# AMP_LO.net
KiCad netlist of a schematic drawn in Altium Designer
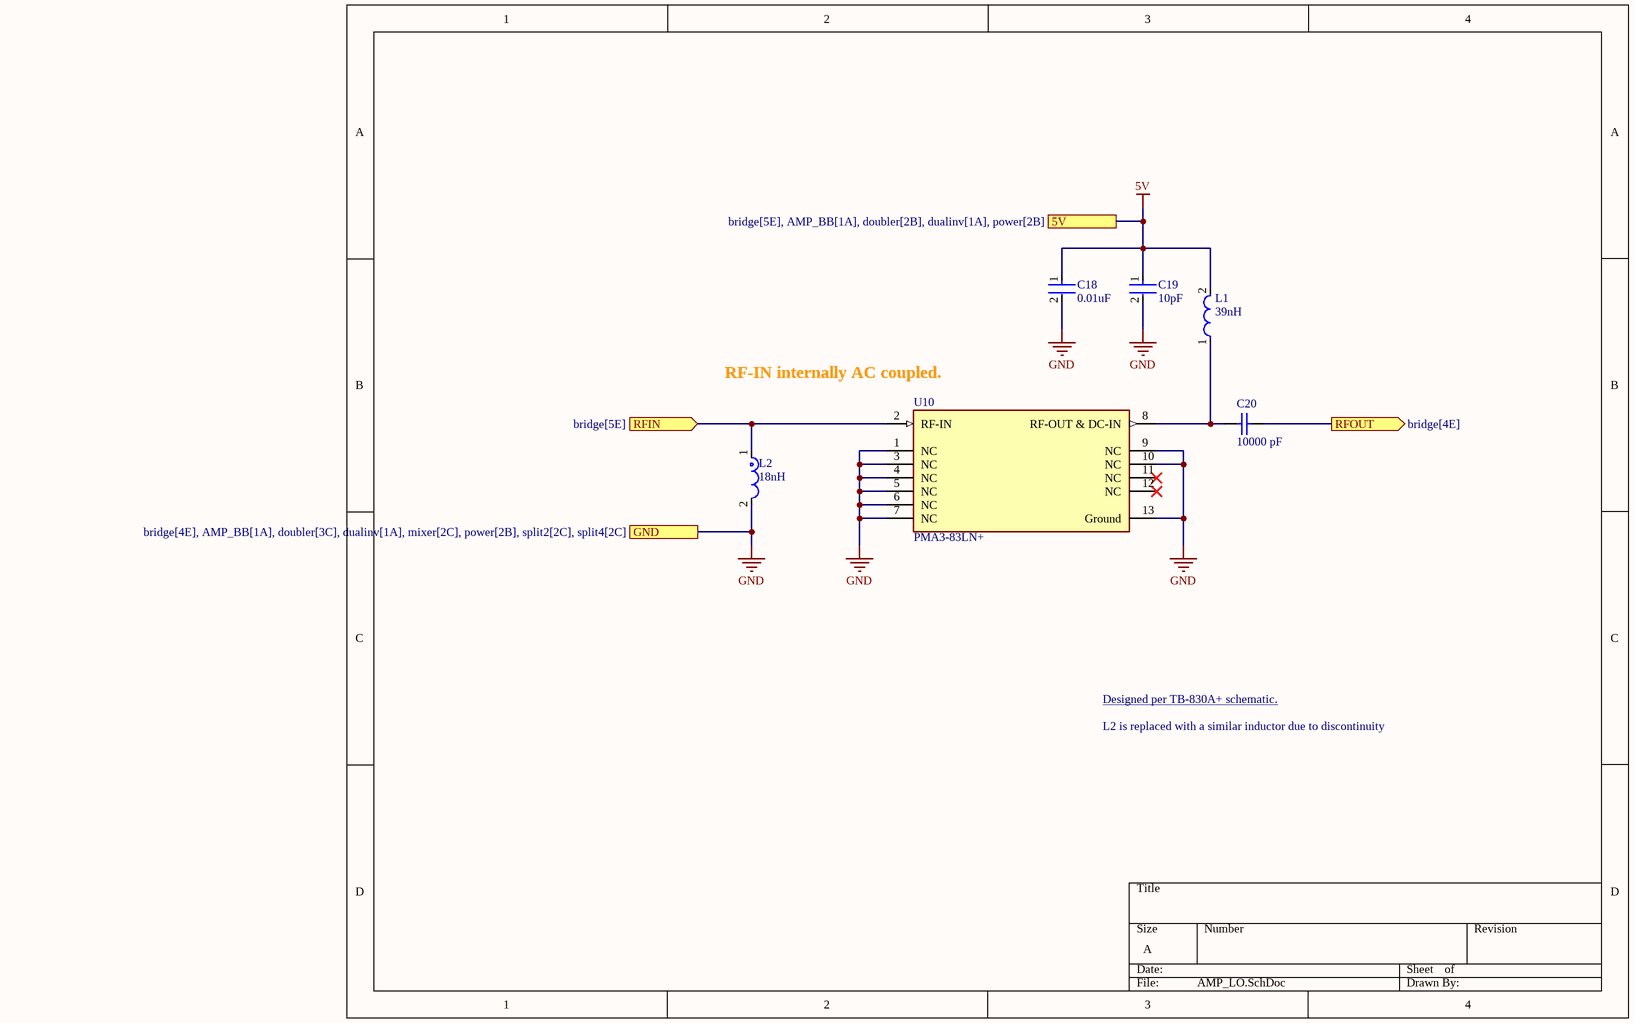
[diagram p0: AMP_LO.SchDoc]

(export (version "E")
  (design (tool "Eeschema 10.0.6"))
  (components
    (comp (ref "C18")
      (value "0.01uF")
      (footprint "FP-C0402-BB-MFG")
      (description "CAP CER 10000PF 50V X7R 0402")
      (fields (field (name "MANUFACTURER") "Murata") (field (name "PART NUMBER") "GCM155R71H103KA55D"))
      (libsource (lib "FullLib") (part "CMP-2008-02109-2"))
    )
    (comp (ref "C19")
      (value "10pF")
      (footprint "FP-GJM155-0_05-IPC_A")
      (description "Multi-Layer Ceramic Capacitor 10pF C0G  ±5% 0402 Paper T/R")
      (fields (field (name "TOLERANCE") "5%") (field (name "VOLTAGE") "50V"))
      (libsource (lib "FullLib") (part "CMP-2008-03797-2"))
    )
    (comp (ref "C20")
      (value "10000 pF")
      (footprint "CAPC1005X55X25ML05T10")
      (description "CAP CER 10000PF 16V X7R 0402, RF Series")
      (fields (field (name "MANUFACTURER") "KYOCERA AVX") (field (name "PART NUMBER") "520L103KT16T"))
      (libsource (lib "FullLib") (part "CNP-CAP-10000PF-RF"))
    )
    (comp (ref "L1")
      (value "39nH")
      (footprint "FP-LQW15AN_00-W0_5-0_1-MFG")
      (description "Wire Wound RF Inductor 39nH ±2% 250mA 0.7Ω 0402 (1005)")
      (fields (field (name "TOLERANCE") "2%") (field (name "PART NUMBER") "LQW15AN39NG00D"))
      (libsource (lib "FullLib") (part "CMP-06042-002147-1"))
    )
    (comp (ref "L2")
      (value "18nH")
      (footprint "FP-LQG15HH_02-MFG")
      (description "Multilayer type RF Inductor 18nH ±5% 0.36Ω 400mA 0402")
      (fields (field (name "TOLERANCE") "5%") (field (name "PART NUMBER") "LQG15HS18NJ02D"))
      (libsource (lib "FullLib") (part "CMP-06042-000668-1"))
    )
    (comp (ref "U10")
      (value "PMA3-83LN+")
      (footprint "FP-DQ1225-MFG")
      (description "SMT LOW NOISE AMPLIFIER, 500 - 8")
      (fields (field (name "MANUFACTURER") "Mini-Circuits"))
      (libsource (lib "FullLib") (part "CMP-199891-000002-1"))
    )
  )
  (nets
    (net (code "1") (name "/RFIN") (class "Default")
      (node (ref "L2") (pin "1") (pinfunction "1_1") (pintype "passive"))
      (node (ref "U10") (pin "2") (pinfunction "RF-IN_2") (pintype "input"))
    )
    (net (code "2") (name "/RFOUT") (class "Default")
      (node (ref "C20") (pin "2") (pinfunction "2_2") (pintype "passive"))
    )
    (net (code "3") (name "5V") (class "Default")
      (node (ref "C18") (pin "1") (pinfunction "1_1") (pintype "passive"))
      (node (ref "C19") (pin "1") (pinfunction "1_1") (pintype "passive"))
      (node (ref "L1") (pin "2") (pinfunction "2_2") (pintype "passive"))
    )
    (net (code "4") (name "GND") (class "Default")
      (node (ref "C18") (pin "2") (pinfunction "2_2") (pintype "passive"))
      (node (ref "C19") (pin "2") (pinfunction "2_2") (pintype "passive"))
      (node (ref "L2") (pin "2") (pinfunction "2_2") (pintype "passive"))
      (node (ref "U10") (pin "1") (pinfunction "NC_1") (pintype "passive"))
      (node (ref "U10") (pin "10") (pinfunction "NC_10") (pintype "passive"))
      (node (ref "U10") (pin "13") (pinfunction "Ground_13") (pintype "power_in"))
      (node (ref "U10") (pin "3") (pinfunction "NC_3") (pintype "passive"))
      (node (ref "U10") (pin "4") (pinfunction "NC_4") (pintype "passive"))
      (node (ref "U10") (pin "5") (pinfunction "NC_5") (pintype "passive"))
      (node (ref "U10") (pin "6") (pinfunction "NC_6") (pintype "passive"))
      (node (ref "U10") (pin "7") (pinfunction "NC_7") (pintype "passive"))
      (node (ref "U10") (pin "9") (pinfunction "NC_9") (pintype "passive"))
    )
    (net (code "5") (name "Net-(U10-RF-OUT_&_DC-IN)") (class "Default")
      (node (ref "C20") (pin "1") (pinfunction "1_1") (pintype "passive"))
      (node (ref "L1") (pin "1") (pinfunction "1_1") (pintype "passive"))
      (node (ref "U10") (pin "8") (pinfunction "RF-OUT_&_DC-IN_8") (pintype "output"))
    )
    (net (code "6") (name "unconnected-(U10-NC-Pad11)") (class "Default")
      (node (ref "U10") (pin "11") (pinfunction "NC_11") (pintype "passive+no_connect"))
    )
    (net (code "7") (name "unconnected-(U10-NC-Pad12)") (class "Default")
      (node (ref "U10") (pin "12") (pinfunction "NC_12") (pintype "passive+no_connect"))
    )
  )
)
